# humanoid-16.net
KiCad netlist of a schematic drawn in EAGLE
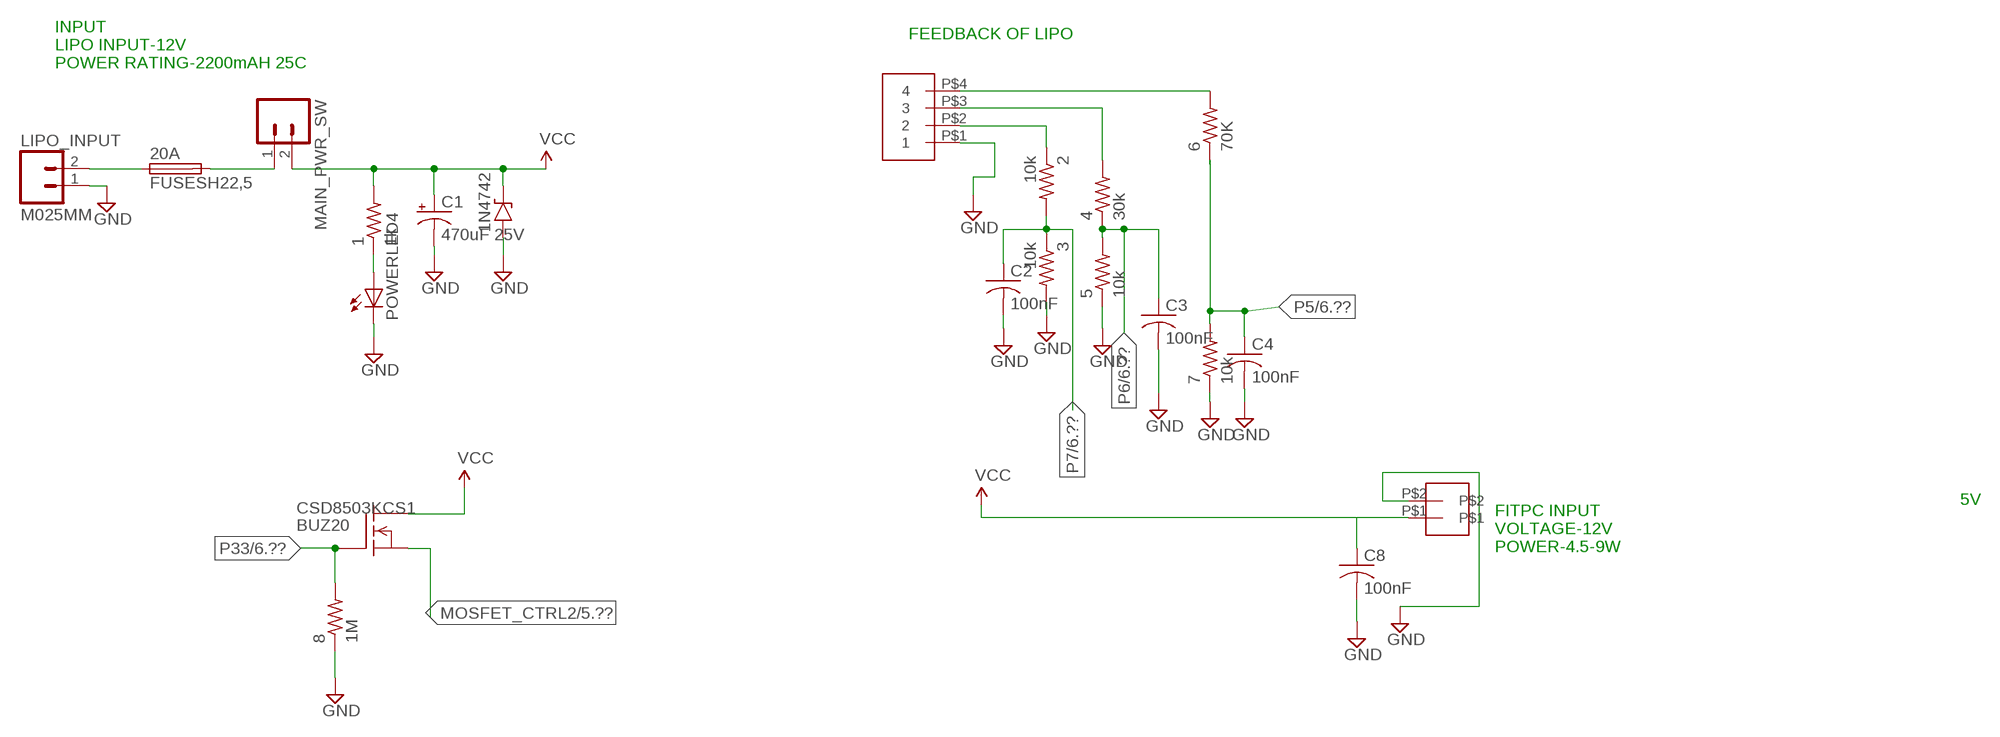
[diagram p0: schematic, sheet 1]
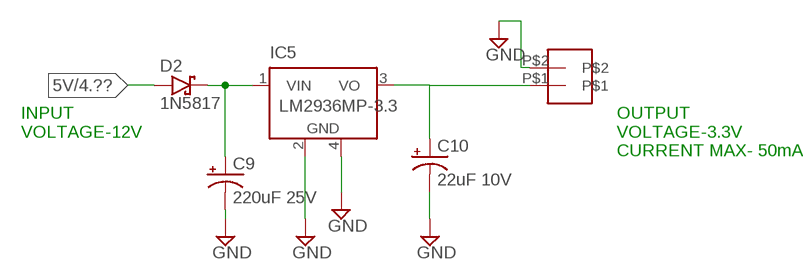
[diagram p1: schematic, sheet 2]
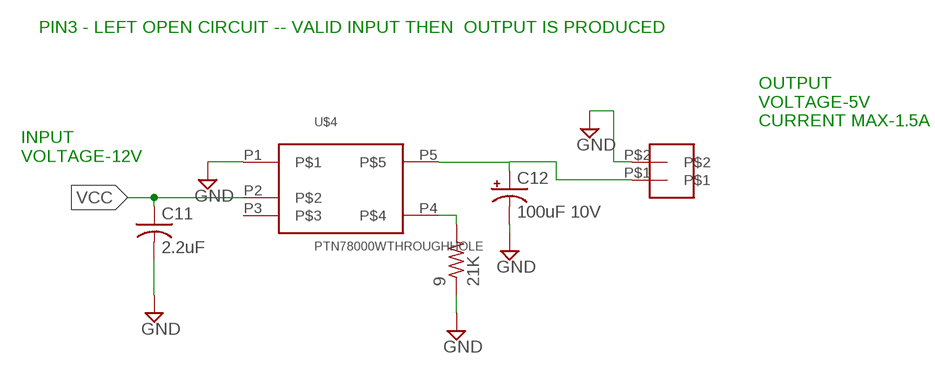
[diagram p2: schematic, sheet 3]
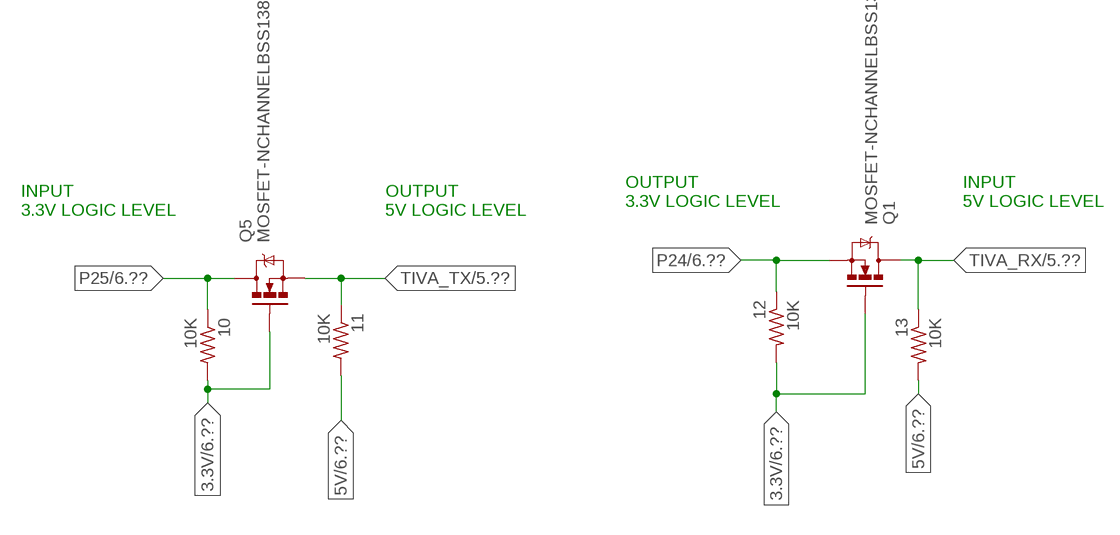
[diagram p3: schematic, sheet 4]
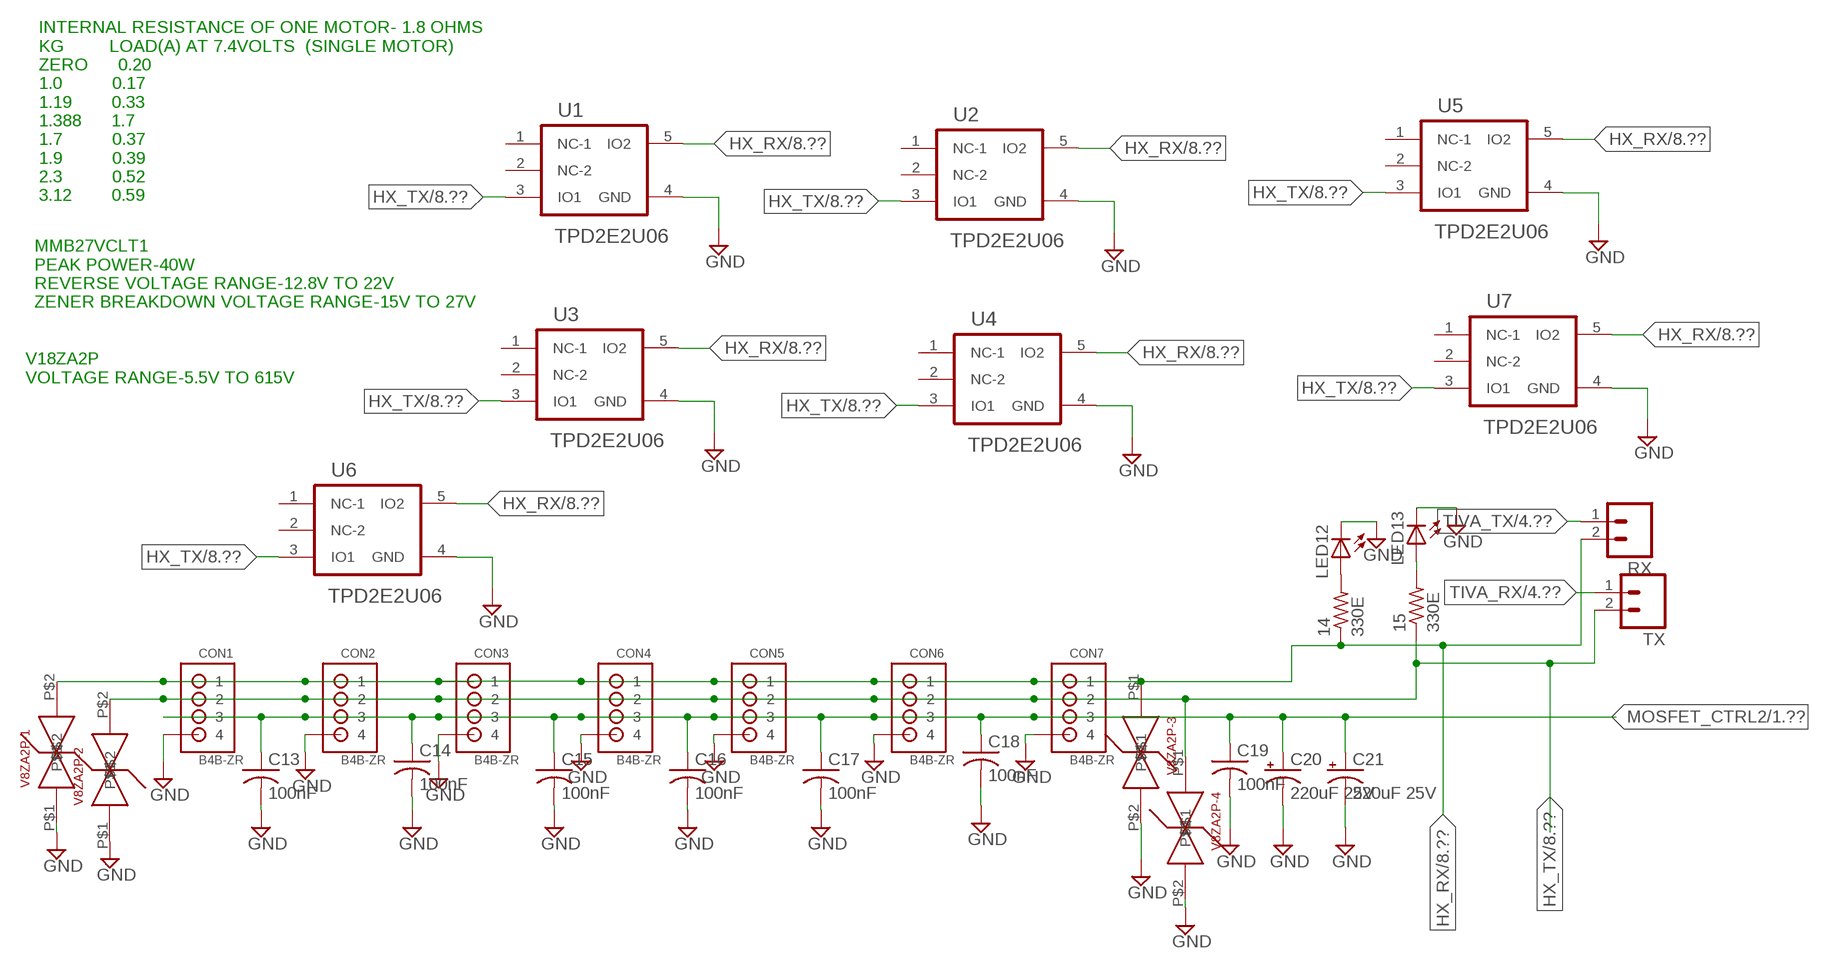
[diagram p4: schematic, sheet 5]
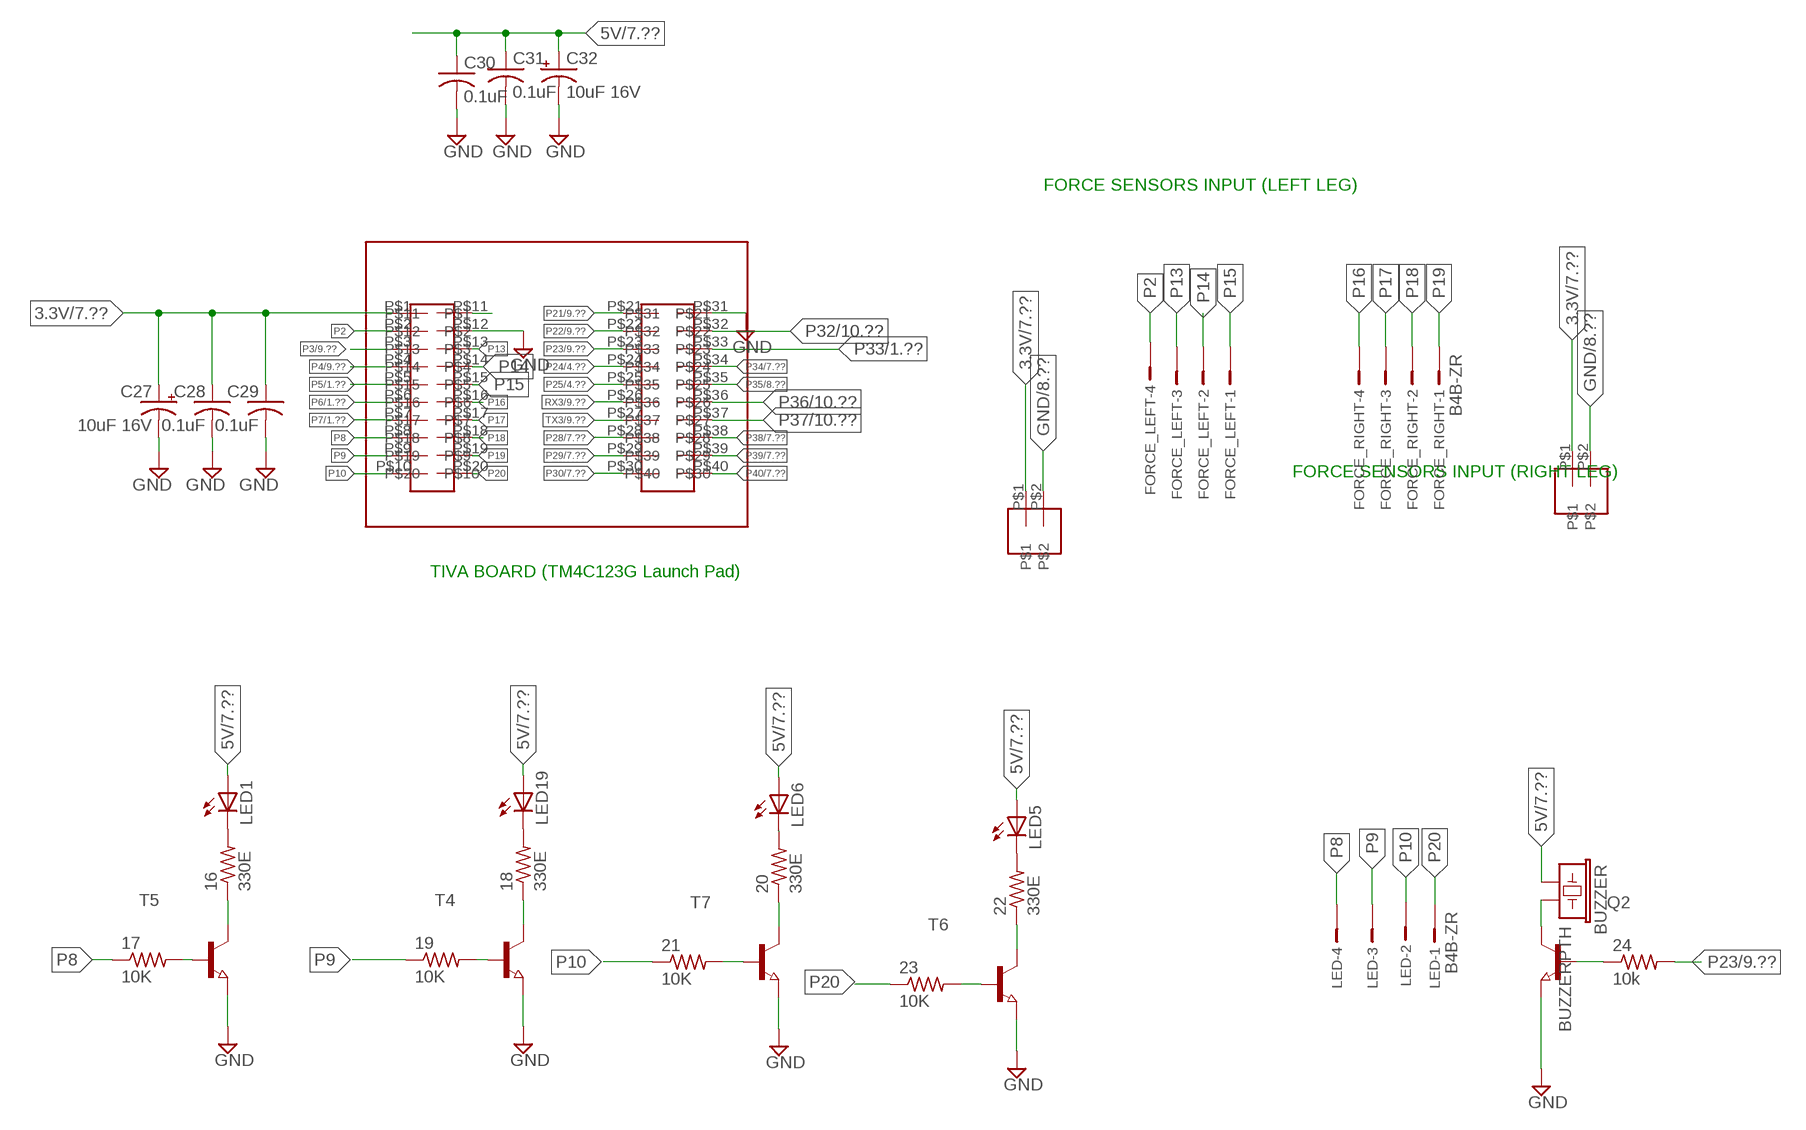
[diagram p5: schematic, sheet 6]
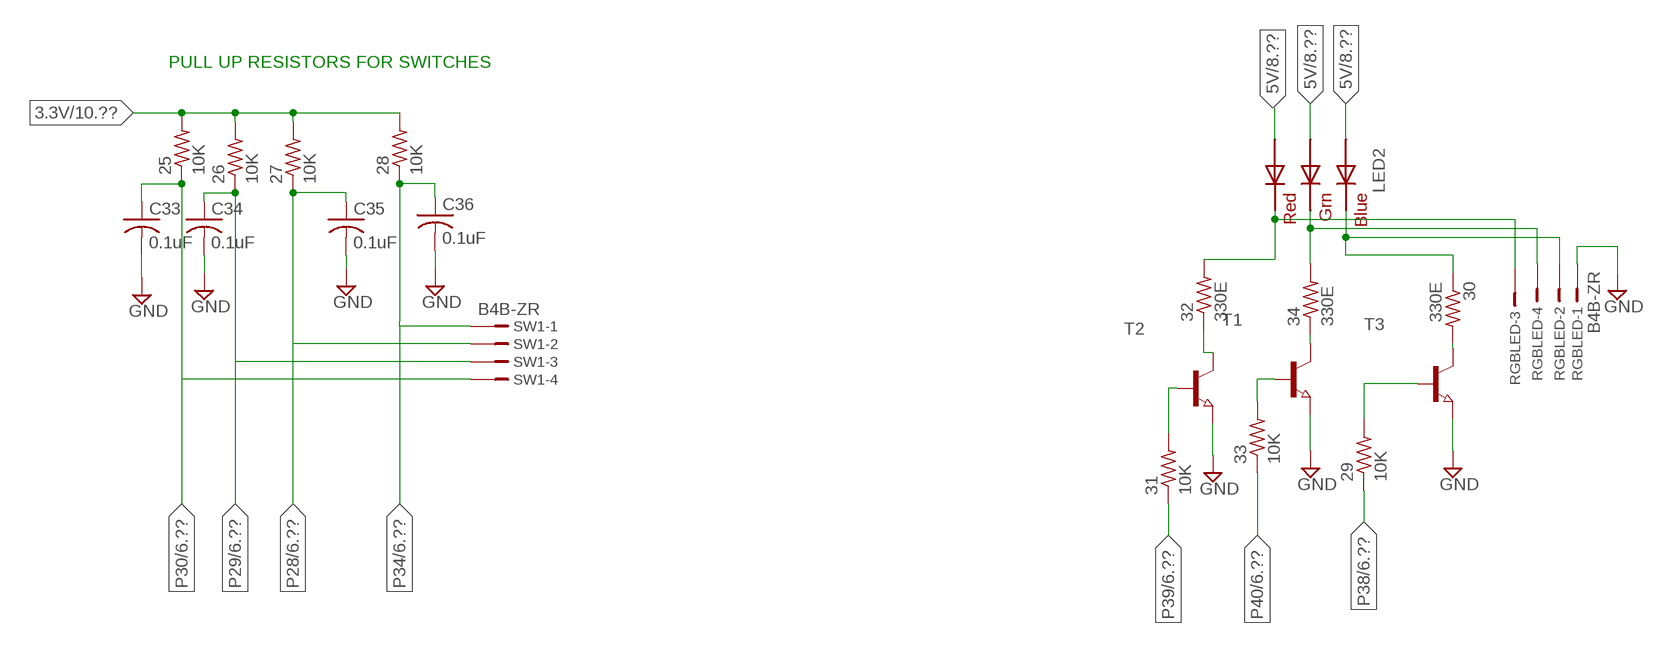
[diagram p6: schematic, sheet 7]
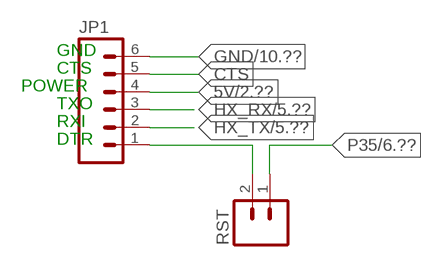
[diagram p7: schematic, sheet 8]
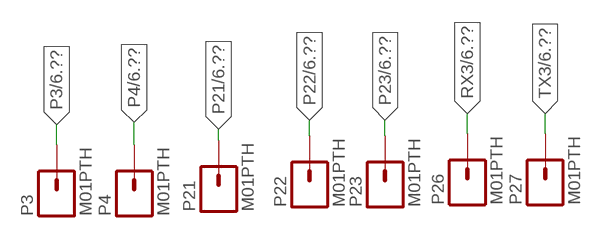
[diagram p8: schematic, sheet 9]
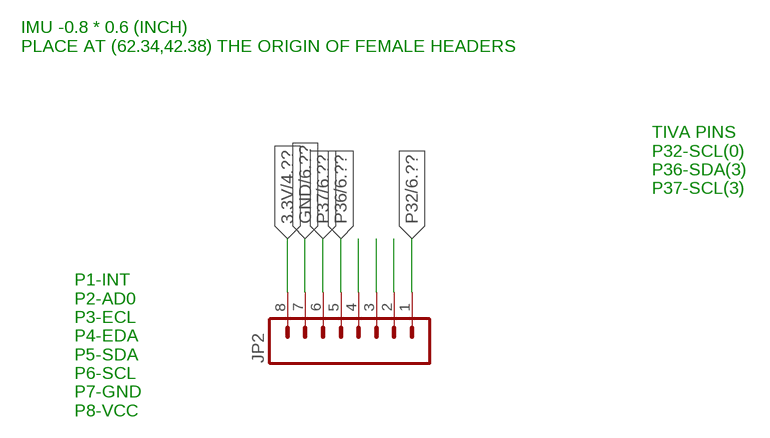
[diagram p9: schematic, sheet 10]

(export (version "E")
  (design (tool "Eeschema 10.0.6"))
  (components
    (comp (ref "3.3VL")
      (value "2PINRIGHT")
      (footprint "eagle-import:2PINRIGHT")
      (libsource (lib "eagle-import") (part "2PINRIGHT"))
    )
    (comp (ref "3.3VR")
      (value "2PINRIGHT")
      (footprint "eagle-import:2PINRIGHT")
      (libsource (lib "eagle-import") (part "2PINRIGHT"))
    )
    (comp (ref "16")
      (value "330E")
      (footprint "eagle-import:R0805")
      (libsource (lib "eagle-import") (part "R-US_R0805"))
    )
    (comp (ref "17")
      (value "10K")
      (footprint "eagle-import:R0805")
      (libsource (lib "eagle-import") (part "R-US_R0805"))
    )
    (comp (ref "18")
      (value "330E")
      (footprint "eagle-import:R0805")
      (libsource (lib "eagle-import") (part "R-US_R0805"))
    )
    (comp (ref "19")
      (value "10K")
      (footprint "eagle-import:R0805")
      (libsource (lib "eagle-import") (part "R-US_R0805"))
    )
    (comp (ref "20")
      (value "330E")
      (footprint "eagle-import:R0805")
      (libsource (lib "eagle-import") (part "R-US_R0805"))
    )
    (comp (ref "21")
      (value "10K")
      (footprint "eagle-import:R0805")
      (libsource (lib "eagle-import") (part "R-US_R0805"))
    )
    (comp (ref "22")
      (value "330E")
      (footprint "eagle-import:R0805")
      (libsource (lib "eagle-import") (part "R-US_R0805"))
    )
    (comp (ref "23")
      (value "10K")
      (footprint "eagle-import:R0805")
      (libsource (lib "eagle-import") (part "R-US_R0805"))
    )
    (comp (ref "24")
      (value "10k")
      (footprint "eagle-import:R0805")
      (libsource (lib "eagle-import") (part "R-US_R0805"))
    )
    (comp (ref "BUZZER")
      (value "BUZZERPTH")
      (footprint "eagle-import:BUZZER-12MM")
      (libsource (lib "eagle-import") (part "BUZZERPTH"))
    )
    (comp (ref "C27")
      (value "10uF 16V")
      (footprint "eagle-import:PANASONIC_B")
      (libsource (lib "eagle-import") (part "CPOL-USB"))
    )
    (comp (ref "C28")
      (value "0.1uF")
      (footprint "eagle-import:C1206")
      (libsource (lib "eagle-import") (part "resistor_C-USC1206"))
    )
    (comp (ref "C29")
      (value "0.1uF")
      (footprint "eagle-import:C1206")
      (libsource (lib "eagle-import") (part "resistor_C-USC1206"))
    )
    (comp (ref "C30")
      (value "0.1uF")
      (footprint "eagle-import:C1206")
      (libsource (lib "eagle-import") (part "resistor_C-USC1206"))
    )
    (comp (ref "C31")
      (value "0.1uF")
      (footprint "eagle-import:C1206")
      (libsource (lib "eagle-import") (part "resistor_C-USC1206"))
    )
    (comp (ref "C32")
      (value "10uF 16V")
      (footprint "eagle-import:PANASONIC_B")
      (libsource (lib "eagle-import") (part "CPOL-USB"))
    )
    (comp (ref "FORCE_LEFT")
      (value "B4B-ZR")
      (footprint "eagle-import:B4B-ZR")
      (fields
        (field (name "MF") "FARNELL")
        (field (name "MPN") "B4B-ZR(LF)(SN)")
        (field (name "OC_NEWARK") "unknown")
      )
      (libsource (lib "eagle-import") (part "?4B-ZRB"))
    )
    (comp (ref "FORCE_RIGHT")
      (value "B4B-ZR")
      (footprint "eagle-import:B4B-ZR")
      (fields
        (field (name "MF") "FARNELL")
        (field (name "MPN") "B4B-ZR(LF)(SN)")
        (field (name "OC_NEWARK") "unknown")
      )
      (libsource (lib "eagle-import") (part "?4B-ZRB"))
    )
    (comp (ref "LED")
      (value "B4B-ZR")
      (footprint "eagle-import:B4B-ZR")
      (fields
        (field (name "MF") "FARNELL")
        (field (name "MPN") "B4B-ZR(LF)(SN)")
        (field (name "OC_NEWARK") "unknown")
      )
      (libsource (lib "eagle-import") (part "?4B-ZRB"))
    )
    (comp (ref "LED1")
      (value "LEDCHIPLED_1206")
      (footprint "eagle-import:CHIPLED_1206")
      (libsource (lib "eagle-import") (part "LEDCHIPLED_1206"))
    )
    (comp (ref "LED5")
      (value "LEDCHIPLED_1206")
      (footprint "eagle-import:CHIPLED_1206")
      (libsource (lib "eagle-import") (part "LEDCHIPLED_1206"))
    )
    (comp (ref "LED6")
      (value "LEDCHIPLED_1206")
      (footprint "eagle-import:CHIPLED_1206")
      (libsource (lib "eagle-import") (part "LEDCHIPLED_1206"))
    )
    (comp (ref "LED19")
      (value "LEDCHIPLED_1206")
      (footprint "eagle-import:CHIPLED_1206")
      (libsource (lib "eagle-import") (part "LEDCHIPLED_1206"))
    )
    (comp (ref "Q2")
      (value "NPN-TRANSISTOR_SOT23")
      (footprint "eagle-import:SOT23")
      (libsource (lib "eagle-import") (part "NPN-TRANSISTOR_SOT23"))
    )
    (comp (ref "T4")
      (value "NPN-TRANSISTOR_SOT23")
      (footprint "eagle-import:SOT23")
      (libsource (lib "eagle-import") (part "NPN-TRANSISTOR_SOT23"))
    )
    (comp (ref "T5")
      (value "NPN-TRANSISTOR_SOT23")
      (footprint "eagle-import:SOT23")
      (libsource (lib "eagle-import") (part "NPN-TRANSISTOR_SOT23"))
    )
    (comp (ref "T6")
      (value "NPN-TRANSISTOR_SOT23")
      (footprint "eagle-import:SOT23")
      (libsource (lib "eagle-import") (part "NPN-TRANSISTOR_SOT23"))
    )
    (comp (ref "T7")
      (value "NPN-TRANSISTOR_SOT23")
      (footprint "eagle-import:SOT23")
      (libsource (lib "eagle-import") (part "NPN-TRANSISTOR_SOT23"))
    )
    (comp (ref "U$1")
      (value "TIVA")
      (footprint "eagle-import:TIVA")
      (libsource (lib "eagle-import") (part "TIVA"))
    )
    (comp (ref "10")
      (value "10K")
      (footprint "eagle-import:R0805")
      (libsource (lib "eagle-import") (part "R-US_R0805"))
    )
    (comp (ref "11")
      (value "10K")
      (footprint "eagle-import:R0805")
      (libsource (lib "eagle-import") (part "R-US_R0805"))
    )
    (comp (ref "12")
      (value "10K")
      (footprint "eagle-import:R0805")
      (libsource (lib "eagle-import") (part "R-US_R0805"))
    )
    (comp (ref "13")
      (value "10K")
      (footprint "eagle-import:R0805")
      (libsource (lib "eagle-import") (part "R-US_R0805"))
    )
    (comp (ref "Q1")
      (value "MOSFET-NCHANNELBSS138")
      (footprint "eagle-import:SOT23")
      (libsource (lib "eagle-import") (part "MOSFET-NCHANNELBSS138"))
    )
    (comp (ref "Q5")
      (value "MOSFET-NCHANNELBSS138")
      (footprint "eagle-import:SOT23")
      (libsource (lib "eagle-import") (part "MOSFET-NCHANNELBSS138"))
    )
    (comp (ref "14")
      (value "330E")
      (footprint "eagle-import:R0805")
      (libsource (lib "eagle-import") (part "R-US_R0805"))
    )
    (comp (ref "15")
      (value "330E")
      (footprint "eagle-import:R0805")
      (libsource (lib "eagle-import") (part "R-US_R0805"))
    )
    (comp (ref "C13")
      (value "100nF")
      (footprint "eagle-import:C1206")
      (fields (field (name "MANUFACTURER") "KEMET") (field (name "PARTNO") "C1206C104K5RACTU"))
      (libsource (lib "eagle-import") (part "C-USC1206"))
    )
    (comp (ref "C14")
      (value "100nF")
      (footprint "eagle-import:C1206")
      (fields (field (name "MANUFACTURER") "KEMET") (field (name "PARTNO") "C1206C104K5RACTU"))
      (libsource (lib "eagle-import") (part "C-USC1206"))
    )
    (comp (ref "C15")
      (value "100nF")
      (footprint "eagle-import:C1206")
      (fields (field (name "MANUFACTURER") "KEMET") (field (name "PARTNO") "C1206C104K5RACTU"))
      (libsource (lib "eagle-import") (part "C-USC1206"))
    )
    (comp (ref "C16")
      (value "100nF")
      (footprint "eagle-import:C1206")
      (fields (field (name "MANUFACTURER") "KEMET") (field (name "PARTNO") "C1206C104K5RACTU"))
      (libsource (lib "eagle-import") (part "C-USC1206"))
    )
    (comp (ref "C17")
      (value "100nF")
      (footprint "eagle-import:C1206")
      (fields (field (name "MANUFACTURER") "KEMET") (field (name "PARTNO") "C1206C104K5RACTU"))
      (libsource (lib "eagle-import") (part "C-USC1206"))
    )
    (comp (ref "C18")
      (value "100nF")
      (footprint "eagle-import:C1206")
      (fields (field (name "MANUFACTURER") "KEMET") (field (name "PARTNO") "C1206C104K5RACTU"))
      (libsource (lib "eagle-import") (part "C-USC1206"))
    )
    (comp (ref "C19")
      (value "100nF")
      (footprint "eagle-import:C1206")
      (fields (field (name "MANUFACTURER") "KEMET") (field (name "PARTNO") "C1206C104K5RACTU"))
      (libsource (lib "eagle-import") (part "C-USC1206"))
    )
    (comp (ref "C20")
      (value "220uF 25V")
      (footprint "eagle-import:PANASONIC_G")
      (fields
        (field (name "MANUFACTURER") " PANASONIC ELECTRONIC COMPONENTS")
        (field (name "MOUSER_PARTNO") "667-EEE-1EA221P")
        (field (name "PARTNO") "EEE-1EA221P")
      )
      (libsource (lib "eagle-import") (part "CPOL-USG"))
    )
    (comp (ref "C21")
      (value "220uF 25V")
      (footprint "eagle-import:PANASONIC_G")
      (fields
        (field (name "MANUFACTURER") " PANASONIC ELECTRONIC COMPONENTS")
        (field (name "MOUSER_PARTNO") "667-EEE-1EA221P")
        (field (name "PARTNO") "EEE-1EA221P")
      )
      (libsource (lib "eagle-import") (part "CPOL-USG"))
    )
    (comp (ref "CON1")
      (value "B4B-ZR")
      (footprint "eagle-import:B4B-ZR")
      (fields (field (name "MF") "FARNELL") (field (name "MPN") "B4B-ZR(LF)(SN)"))
      (libsource (lib "eagle-import") (part "B4B-ZR"))
    )
    (comp (ref "CON2")
      (value "B4B-ZR")
      (footprint "eagle-import:B4B-ZR")
      (fields (field (name "MF") "FARNELL") (field (name "MPN") "B4B-ZR(LF)(SN)"))
      (libsource (lib "eagle-import") (part "B4B-ZR"))
    )
    (comp (ref "CON3")
      (value "B4B-ZR")
      (footprint "eagle-import:B4B-ZR")
      (fields (field (name "MF") "FARNELL") (field (name "MPN") "B4B-ZR(LF)(SN)"))
      (libsource (lib "eagle-import") (part "B4B-ZR"))
    )
    (comp (ref "CON4")
      (value "B4B-ZR")
      (footprint "eagle-import:B4B-ZR")
      (fields (field (name "MF") "FARNELL") (field (name "MPN") "B4B-ZR(LF)(SN)"))
      (libsource (lib "eagle-import") (part "B4B-ZR"))
    )
    (comp (ref "CON5")
      (value "B4B-ZR")
      (footprint "eagle-import:B4B-ZR")
      (fields (field (name "MF") "FARNELL") (field (name "MPN") "B4B-ZR(LF)(SN)"))
      (libsource (lib "eagle-import") (part "B4B-ZR"))
    )
    (comp (ref "CON6")
      (value "B4B-ZR")
      (footprint "eagle-import:B4B-ZR")
      (fields (field (name "MF") "FARNELL") (field (name "MPN") "B4B-ZR(LF)(SN)"))
      (libsource (lib "eagle-import") (part "B4B-ZR"))
    )
    (comp (ref "CON7")
      (value "B4B-ZR")
      (footprint "eagle-import:B4B-ZR")
      (fields (field (name "MF") "FARNELL") (field (name "MPN") "B4B-ZR(LF)(SN)"))
      (libsource (lib "eagle-import") (part "B4B-ZR"))
    )
    (comp (ref "LED12")
      (value "LEDCHIPLED_1206")
      (footprint "eagle-import:CHIPLED_1206")
      (libsource (lib "eagle-import") (part "LEDCHIPLED_1206"))
    )
    (comp (ref "LED13")
      (value "LEDCHIPLED_1206")
      (footprint "eagle-import:CHIPLED_1206")
      (libsource (lib "eagle-import") (part "LEDCHIPLED_1206"))
    )
    (comp (ref "RX")
      (value "M02PTH")
      (footprint "eagle-import:1X02")
      (libsource (lib "eagle-import") (part "M02PTH"))
    )
    (comp (ref "TX")
      (value "M02PTH")
      (footprint "eagle-import:1X02")
      (libsource (lib "eagle-import") (part "M02PTH"))
    )
    (comp (ref "U1")
      (value "TPD2E2U06")
      (footprint "eagle-import:SOT50P160X60-5N")
      (fields (field (name "MPN") "TPD2E001IDRLRQ1"))
      (libsource (lib "eagle-import") (part "TPD2E2U06"))
    )
    (comp (ref "U2")
      (value "TPD2E2U06")
      (footprint "eagle-import:SOT50P160X60-5N")
      (fields (field (name "MPN") "TPD2E001IDRLRQ1"))
      (libsource (lib "eagle-import") (part "TPD2E2U06"))
    )
    (comp (ref "U3")
      (value "TPD2E2U06")
      (footprint "eagle-import:SOT50P160X60-5N")
      (fields (field (name "MPN") "TPD2E001IDRLRQ1"))
      (libsource (lib "eagle-import") (part "TPD2E2U06"))
    )
    (comp (ref "U4")
      (value "TPD2E2U06")
      (footprint "eagle-import:SOT50P160X60-5N")
      (fields (field (name "MPN") "TPD2E001IDRLRQ1"))
      (libsource (lib "eagle-import") (part "TPD2E2U06"))
    )
    (comp (ref "U5")
      (value "TPD2E2U06")
      (footprint "eagle-import:SOT50P160X60-5N")
      (fields (field (name "MPN") "TPD2E001IDRLRQ1"))
      (libsource (lib "eagle-import") (part "TPD2E2U06"))
    )
    (comp (ref "U6")
      (value "TPD2E2U06")
      (footprint "eagle-import:SOT50P160X60-5N")
      (fields (field (name "MPN") "TPD2E001IDRLRQ1"))
      (libsource (lib "eagle-import") (part "TPD2E2U06"))
    )
    (comp (ref "U7")
      (value "TPD2E2U06")
      (footprint "eagle-import:SOT50P160X60-5N")
      (fields (field (name "MPN") "TPD2E001IDRLRQ1"))
      (libsource (lib "eagle-import") (part "TPD2E2U06"))
    )
    (comp (ref "V8ZA2P-1")
      (value "V18ZA2P")
      (footprint "eagle-import:V18ZA2P")
      (libsource (lib "eagle-import") (part "V18ZA2P"))
    )
    (comp (ref "V8ZA2P-2")
      (value "V18ZA2P")
      (footprint "eagle-import:V18ZA2P")
      (libsource (lib "eagle-import") (part "V18ZA2P"))
    )
    (comp (ref "V8ZA2P-3")
      (value "V18ZA2P")
      (footprint "eagle-import:V18ZA2P")
      (libsource (lib "eagle-import") (part "V18ZA2P"))
    )
    (comp (ref "V8ZA2P-4")
      (value "V18ZA2P")
      (footprint "eagle-import:V18ZA2P")
      (libsource (lib "eagle-import") (part "V18ZA2P"))
    )
    (comp (ref "1")
      (value "1k")
      (footprint "eagle-import:R0805")
      (libsource (lib "eagle-import") (part "R-US_R0805"))
    )
    (comp (ref "1N4742")
      (value "1N47XX3")
      (footprint "eagle-import:DO41-3")
      (libsource (lib "eagle-import") (part "1N47XX3"))
    )
    (comp (ref "2")
      (value "10k")
      (footprint "eagle-import:R0805")
      (libsource (lib "eagle-import") (part "R-US_R0805"))
    )
    (comp (ref "3")
      (value "10k")
      (footprint "eagle-import:R0805")
      (libsource (lib "eagle-import") (part "R-US_R0805"))
    )
    (comp (ref "4")
      (value "30k")
      (footprint "eagle-import:R0805")
      (libsource (lib "eagle-import") (part "R-US_R0805"))
    )
    (comp (ref "5")
      (value "10k")
      (footprint "eagle-import:R0805")
      (libsource (lib "eagle-import") (part "R-US_R0805"))
    )
    (comp (ref "6")
      (value "70K")
      (footprint "eagle-import:R0805")
      (libsource (lib "eagle-import") (part "R-US_R0805"))
    )
    (comp (ref "7")
      (value "10k")
      (footprint "eagle-import:R0805")
      (libsource (lib "eagle-import") (part "R-US_R0805"))
    )
    (comp (ref "8")
      (value "1M")
      (footprint "eagle-import:R0805")
      (libsource (lib "eagle-import") (part "R-US_R0805"))
    )
    (comp (ref "20A")
      (value "FUSESH22,5")
      (footprint "eagle-import:SH22,5")
      (libsource (lib "eagle-import") (part "FUSESH22,5"))
    )
    (comp (ref "C1")
      (value "470uF 25V")
      (footprint "eagle-import:PANASONIC_G")
      (fields
        (field (name "MANUFACTURER") " PANASONIC ELECTRONIC COMPONENTS")
        (field (name "PARTNO") "EEEFK1E471AP")
      )
      (libsource (lib "eagle-import") (part "CPOL-USG"))
    )
    (comp (ref "C2")
      (value "100nF")
      (footprint "eagle-import:C1206")
      (fields (field (name "MANUFACTURER") "KEMET") (field (name "PARTNO") "C1206C104K5RACTU"))
      (libsource (lib "eagle-import") (part "C-USC1206"))
    )
    (comp (ref "C3")
      (value "100nF")
      (footprint "eagle-import:C1206")
      (fields (field (name "MANUFACTURER") "KEMET") (field (name "PARTNO") "C1206C104K5RACTU"))
      (libsource (lib "eagle-import") (part "C-USC1206"))
    )
    (comp (ref "C4")
      (value "100nF")
      (footprint "eagle-import:C1206")
      (fields (field (name "MANUFACTURER") "KEMET") (field (name "PARTNO") "C1206C104K5RACTU"))
      (libsource (lib "eagle-import") (part "C-USC1206"))
    )
    (comp (ref "C8")
      (value "100nF")
      (footprint "eagle-import:C1206")
      (fields (field (name "MANUFACTURER") "KEMET") (field (name "PARTNO") "C1206C104K5RACTU"))
      (libsource (lib "eagle-import") (part "C-USC1206"))
    )
    (comp (ref "CSD8503KCS1")
      (value "BUZ20")
      (footprint "eagle-import:TO220")
      (libsource (lib "eagle-import") (part "BUZ20"))
    )
    (comp (ref "FITPC")
      (value "2PINRIGHT")
      (footprint "eagle-import:2PINRIGHT")
      (libsource (lib "eagle-import") (part "2PINRIGHT"))
    )
    (comp (ref "LIPO_INPUT")
      (value "M025MM")
      (footprint "eagle-import:SCREWTERMINAL-5MM-2")
      (libsource (lib "eagle-import") (part "SparkFun-Connectors_M025MM"))
    )
    (comp (ref "MAIN_PWR_SW")
      (value "M02PTH")
      (footprint "eagle-import:1X02")
      (libsource (lib "eagle-import") (part "M02PTH"))
    )
    (comp (ref "POWERLED4")
      (value "LEDCHIPLED_1206")
      (footprint "eagle-import:CHIPLED_1206")
      (libsource (lib "eagle-import") (part "LEDCHIPLED_1206"))
    )
    (comp (ref "U$2")
      (value "4PINRIGHT")
      (footprint "eagle-import:4PINRIGHT")
      (libsource (lib "eagle-import") (part "4PINRIGHT"))
    )
    (comp (ref "JP1")
      (value "M06LOCK")
      (footprint "eagle-import:1X06_LOCK")
      (libsource (lib "eagle-import") (part "M06LOCK"))
    )
    (comp (ref "RST")
      (value "M02PTH")
      (footprint "eagle-import:1X02")
      (libsource (lib "eagle-import") (part "M02PTH"))
    )
    (comp (ref "5V1")
      (value "2PINRIGHT")
      (footprint "eagle-import:2PINRIGHT")
      (libsource (lib "eagle-import") (part "2PINRIGHT"))
    )
    (comp (ref "9")
      (value "21K")
      (footprint "eagle-import:R0805")
      (libsource (lib "eagle-import") (part "R-US_R0805"))
    )
    (comp (ref "C11")
      (value "2.2uF")
      (footprint "eagle-import:C1206")
      (fields
        (field (name "MANUFACTURER") "TDK")
        (field (name "MOUSER_PARTNO") "810-C1608X7R1A225K")
        (field (name "PARTNO") "C1608X7R1A225K080AC")
      )
      (libsource (lib "eagle-import") (part "resistor_C-USC1206"))
    )
    (comp (ref "C12")
      (value "100uF 10V")
      (footprint "eagle-import:PANASONIC_E")
      (fields
        (field (name "MANUFACTURER") "Panasonic")
        (field (name "MOUSER_PARTNO") " 667-EEE-HA1A101P")
        (field (name "PARTNO") "EEE-HA1A101P")
      )
      (libsource (lib "eagle-import") (part "CPOL-USE"))
    )
    (comp (ref "U$4")
      (value "PTN78000WTHROUGHHOLE")
      (footprint "eagle-import:PTN78000W")
      (libsource (lib "eagle-import") (part "PTN78000WTHROUGHHOLE"))
    )
    (comp (ref "25")
      (value "10K")
      (footprint "eagle-import:R0805")
      (libsource (lib "eagle-import") (part "R-US_R0805"))
    )
    (comp (ref "26")
      (value "10K")
      (footprint "eagle-import:R0805")
      (libsource (lib "eagle-import") (part "R-US_R0805"))
    )
    (comp (ref "27")
      (value "10K")
      (footprint "eagle-import:R0805")
      (libsource (lib "eagle-import") (part "R-US_R0805"))
    )
    (comp (ref "28")
      (value "10K")
      (footprint "eagle-import:R0805")
      (libsource (lib "eagle-import") (part "R-US_R0805"))
    )
    (comp (ref "29")
      (value "10K")
      (footprint "eagle-import:R0805")
      (libsource (lib "eagle-import") (part "R-US_R0805"))
    )
    (comp (ref "30")
      (value "330E")
      (footprint "eagle-import:R0805")
      (libsource (lib "eagle-import") (part "R-US_R0805"))
    )
    (comp (ref "31")
      (value "10K")
      (footprint "eagle-import:R0805")
      (libsource (lib "eagle-import") (part "R-US_R0805"))
    )
    (comp (ref "32")
      (value "330E")
      (footprint "eagle-import:R0805")
      (libsource (lib "eagle-import") (part "R-US_R0805"))
    )
    (comp (ref "33")
      (value "10K")
      (footprint "eagle-import:R0805")
      (libsource (lib "eagle-import") (part "R-US_R0805"))
    )
    (comp (ref "34")
      (value "330E")
      (footprint "eagle-import:R0805")
      (libsource (lib "eagle-import") (part "R-US_R0805"))
    )
    (comp (ref "C33")
      (value "0.1uF")
      (footprint "eagle-import:C1206")
      (fields
        (field (name "MANUFACTURER") "Kemet")
        (field (name "MOUSER_PARTNO") "80-C0805C104M5R")
        (field (name "PARTNO") "C0805C104M5RACTU")
      )
      (libsource (lib "eagle-import") (part "C-USC1206"))
    )
    (comp (ref "C34")
      (value "0.1uF")
      (footprint "eagle-import:C1206")
      (fields
        (field (name "MANUFACTURER") "Kemet")
        (field (name "MOUSER_PARTNO") "80-C0805C104M5R")
        (field (name "PARTNO") "C0805C104M5RACTU")
      )
      (libsource (lib "eagle-import") (part "C-USC1206"))
    )
    (comp (ref "C35")
      (value "0.1uF")
      (footprint "eagle-import:C1206")
      (fields
        (field (name "MANUFACTURER") "Kemet")
        (field (name "MOUSER_PARTNO") "80-C0805C104M5R")
        (field (name "PARTNO") "C0805C104M5RACTU")
      )
      (libsource (lib "eagle-import") (part "C-USC1206"))
    )
    (comp (ref "C36")
      (value "0.1uF")
      (footprint "eagle-import:C1206")
      (fields
        (field (name "MANUFACTURER") "Kemet")
        (field (name "MOUSER_PARTNO") "80-C0805C104M5R")
        (field (name "PARTNO") "C0805C104M5RACTU")
      )
      (libsource (lib "eagle-import") (part "C-USC1206"))
    )
    (comp (ref "LED2")
      (value "RGBLED5050")
      (footprint "eagle-import:RGBLED5050")
      (libsource (lib "eagle-import") (part "RGBLED5050"))
    )
    (comp (ref "RGBLED")
      (value "B4B-ZR")
      (footprint "eagle-import:B4B-ZR")
      (fields
        (field (name "MF") "FARNELL")
        (field (name "MPN") "B4B-ZR(LF)(SN)")
        (field (name "OC_NEWARK") "unknown")
      )
      (libsource (lib "eagle-import") (part "?4B-ZRB"))
    )
    (comp (ref "SW1")
      (value "B4B-ZR")
      (footprint "eagle-import:B4B-ZR")
      (fields
        (field (name "MF") "FARNELL")
        (field (name "MPN") "B4B-ZR(LF)(SN)")
        (field (name "OC_NEWARK") "unknown")
      )
      (libsource (lib "eagle-import") (part "?4B-ZRB"))
    )
    (comp (ref "T1")
      (value "NPN-TRANSISTOR_SOT23")
      (footprint "eagle-import:SOT23")
      (libsource (lib "eagle-import") (part "NPN-TRANSISTOR_SOT23"))
    )
    (comp (ref "T2")
      (value "NPN-TRANSISTOR_SOT23")
      (footprint "eagle-import:SOT23")
      (libsource (lib "eagle-import") (part "NPN-TRANSISTOR_SOT23"))
    )
    (comp (ref "T3")
      (value "NPN-TRANSISTOR_SOT23")
      (footprint "eagle-import:SOT23")
      (libsource (lib "eagle-import") (part "NPN-TRANSISTOR_SOT23"))
    )
    (comp (ref "JP2")
      (value "M081X08")
      (footprint "eagle-import:1X08")
      (libsource (lib "eagle-import") (part "M081X08"))
    )
    (comp (ref "P3")
      (value "M01PTH")
      (footprint "eagle-import:1X01")
      (libsource (lib "eagle-import") (part "M01PTH"))
    )
    (comp (ref "P4")
      (value "M01PTH")
      (footprint "eagle-import:1X01")
      (libsource (lib "eagle-import") (part "M01PTH"))
    )
    (comp (ref "P21")
      (value "M01PTH")
      (footprint "eagle-import:1X01")
      (libsource (lib "eagle-import") (part "M01PTH"))
    )
    (comp (ref "P22")
      (value "M01PTH")
      (footprint "eagle-import:1X01")
      (libsource (lib "eagle-import") (part "M01PTH"))
    )
    (comp (ref "P23")
      (value "M01PTH")
      (footprint "eagle-import:1X01")
      (libsource (lib "eagle-import") (part "M01PTH"))
    )
    (comp (ref "P26")
      (value "M01PTH")
      (footprint "eagle-import:1X01")
      (libsource (lib "eagle-import") (part "M01PTH"))
    )
    (comp (ref "P27")
      (value "M01PTH")
      (footprint "eagle-import:1X01")
      (libsource (lib "eagle-import") (part "M01PTH"))
    )
    (comp (ref "3.3V1")
      (value "2PINRIGHT")
      (footprint "eagle-import:2PINRIGHT")
      (libsource (lib "eagle-import") (part "2PINRIGHT"))
    )
    (comp (ref "C9")
      (value "220uF 25V")
      (footprint "eagle-import:PANASONIC_G")
      (fields
        (field (name "MANUFACTURER") " PANASONIC ELECTRONIC COMPONENTS")
        (field (name "MOUSER_PARTNO") "667-EEE-1EA221P")
        (field (name "PARTNO") "EEE-1EA221P")
      )
      (libsource (lib "eagle-import") (part "CPOL-USG"))
    )
    (comp (ref "C10")
      (value "22uF 10V")
      (footprint "eagle-import:PANASONIC_B")
      (fields
        (field (name "MANUFACTURER") " PANASONIC ELECTRONIC COMPONENTS")
        (field (name "PARTNO") "EEEFK1A220AR")
      )
      (libsource (lib "eagle-import") (part "CPOL-USB"))
    )
    (comp (ref "D2")
      (value "1N5817")
      (footprint "eagle-import:DO41-3")
      (libsource (lib "eagle-import") (part "1N5817"))
    )
    (comp (ref "IC5")
      (value "LM2936MP-3.3")
      (footprint "eagle-import:SOT223")
      (fields
        (field (name "MF") "NATIONAL SEMICONDUCTOR")
        (field (name "MPN") "LM2936MP-3.3/NOPB")
        (field (name "OC_NEWARK") "unknown")
      )
      (libsource (lib "eagle-import") (part "LM2936MP?-3.3"))
    )
  )
  (nets
    (net (code "1") (name "3.3V") (class "Default")
      (node (ref "10") (pin "2") (pinfunction "2_2") (pintype "passive"))
      (node (ref "12") (pin "2") (pinfunction "2_2") (pintype "passive"))
      (node (ref "25") (pin "2") (pinfunction "2_2") (pintype "passive"))
      (node (ref "26") (pin "2") (pinfunction "2_2") (pintype "passive"))
      (node (ref "27") (pin "2") (pinfunction "2_2") (pintype "passive"))
      (node (ref "28") (pin "2") (pinfunction "2_2") (pintype "passive"))
      (node (ref "3.3V1") (pin "P$1") (pinfunction "P$1_P$1") (pintype "bidirectional"))
      (node (ref "3.3VL") (pin "P$1") (pinfunction "P$1_P$1") (pintype "bidirectional"))
      (node (ref "3.3VR") (pin "P$1") (pinfunction "P$1_P$1") (pintype "bidirectional"))
      (node (ref "C10") (pin "+") (pinfunction "+_+") (pintype "passive"))
      (node (ref "C27") (pin "+") (pinfunction "+_+") (pintype "passive"))
      (node (ref "C28") (pin "1") (pinfunction "1_1") (pintype "passive"))
      (node (ref "C29") (pin "1") (pinfunction "1_1") (pintype "passive"))
      (node (ref "IC5") (pin "3") (pinfunction "VO_3") (pintype "passive"))
      (node (ref "JP2") (pin "8") (pinfunction "8_8") (pintype "passive"))
      (node (ref "Q1") (pin "1") (pinfunction "G_1") (pintype "passive"))
      (node (ref "Q5") (pin "1") (pinfunction "G_1") (pintype "passive"))
      (node (ref "U$1") (pin "P$1") (pinfunction "P$1_P$1") (pintype "bidirectional"))
    )
    (net (code "2") (name "5V") (class "Default")
      (node (ref "11") (pin "2") (pinfunction "2_2") (pintype "passive"))
      (node (ref "13") (pin "2") (pinfunction "2_2") (pintype "passive"))
      (node (ref "5V1") (pin "P$1") (pinfunction "P$1_P$1") (pintype "bidirectional"))
      (node (ref "BUZZER") (pin "+") (pinfunction "1_+") (pintype "passive"))
      (node (ref "C12") (pin "+") (pinfunction "+_+") (pintype "passive"))
      (node (ref "C30") (pin "1") (pinfunction "1_1") (pintype "passive"))
      (node (ref "C31") (pin "1") (pinfunction "1_1") (pintype "passive"))
      (node (ref "C32") (pin "+") (pinfunction "+_+") (pintype "passive"))
      (node (ref "D2") (pin "A") (pinfunction "A_A") (pintype "passive"))
      (node (ref "JP1") (pin "4") (pinfunction "4_4") (pintype "passive"))
      (node (ref "LED1") (pin "A") (pinfunction "A_A") (pintype "passive"))
      (node (ref "LED19") (pin "A") (pinfunction "A_A") (pintype "passive"))
      (node (ref "LED2") (pin "1") (pinfunction "GREEN_A_1") (pintype "bidirectional"))
      (node (ref "LED2") (pin "2") (pinfunction "RED_A_2") (pintype "bidirectional"))
      (node (ref "LED2") (pin "3") (pinfunction "BLUE_A_3") (pintype "bidirectional"))
      (node (ref "LED5") (pin "A") (pinfunction "A_A") (pintype "passive"))
      (node (ref "LED6") (pin "A") (pinfunction "A_A") (pintype "passive"))
      (node (ref "U$1") (pin "P$11") (pinfunction "P$11_P$11") (pintype "bidirectional"))
      (node (ref "U$4") (pin "P5") (pinfunction "P$5_P5") (pintype "bidirectional"))
    )
    (net (code "3") (name "CTS") (class "Default")
      (node (ref "JP1") (pin "5") (pinfunction "5_5") (pintype "passive"))
    )
    (net (code "4") (name "GND") (class "Default")
      (node (ref "1N4742") (pin "A") (pinfunction "A_A") (pintype "passive"))
      (node (ref "3") (pin "2") (pinfunction "2_2") (pintype "passive"))
      (node (ref "3.3V1") (pin "P$2") (pinfunction "P$2_P$2") (pintype "bidirectional"))
      (node (ref "3.3VL") (pin "P$2") (pinfunction "P$2_P$2") (pintype "bidirectional"))
      (node (ref "3.3VR") (pin "P$2") (pinfunction "P$2_P$2") (pintype "bidirectional"))
      (node (ref "5") (pin "1") (pinfunction "1_1") (pintype "passive"))
      (node (ref "5V1") (pin "P$2") (pinfunction "P$2_P$2") (pintype "bidirectional"))
      (node (ref "7") (pin "1") (pinfunction "1_1") (pintype "passive"))
      (node (ref "8") (pin "1") (pinfunction "1_1") (pintype "passive"))
      (node (ref "9") (pin "1") (pinfunction "1_1") (pintype "passive"))
      (node (ref "C1") (pin "-") (pinfunction "-_-") (pintype "passive"))
      (node (ref "C10") (pin "-") (pinfunction "-_-") (pintype "passive"))
      (node (ref "C11") (pin "2") (pinfunction "2_2") (pintype "passive"))
      (node (ref "C12") (pin "-") (pinfunction "-_-") (pintype "passive"))
      (node (ref "C13") (pin "2") (pinfunction "2_2") (pintype "passive"))
      (node (ref "C14") (pin "2") (pinfunction "2_2") (pintype "passive"))
      (node (ref "C15") (pin "2") (pinfunction "2_2") (pintype "passive"))
      (node (ref "C16") (pin "2") (pinfunction "2_2") (pintype "passive"))
      (node (ref "C17") (pin "2") (pinfunction "2_2") (pintype "passive"))
      (node (ref "C18") (pin "2") (pinfunction "2_2") (pintype "passive"))
      (node (ref "C19") (pin "2") (pinfunction "2_2") (pintype "passive"))
      (node (ref "C2") (pin "2") (pinfunction "2_2") (pintype "passive"))
      (node (ref "C20") (pin "-") (pinfunction "-_-") (pintype "passive"))
      (node (ref "C21") (pin "-") (pinfunction "-_-") (pintype "passive"))
      (node (ref "C27") (pin "-") (pinfunction "-_-") (pintype "passive"))
      (node (ref "C28") (pin "2") (pinfunction "2_2") (pintype "passive"))
      (node (ref "C29") (pin "2") (pinfunction "2_2") (pintype "passive"))
      (node (ref "C3") (pin "2") (pinfunction "2_2") (pintype "passive"))
      (node (ref "C30") (pin "2") (pinfunction "2_2") (pintype "passive"))
      (node (ref "C31") (pin "2") (pinfunction "2_2") (pintype "passive"))
      (node (ref "C32") (pin "-") (pinfunction "-_-") (pintype "passive"))
      (node (ref "C33") (pin "2") (pinfunction "2_2") (pintype "passive"))
      (node (ref "C34") (pin "2") (pinfunction "2_2") (pintype "passive"))
      (node (ref "C35") (pin "2") (pinfunction "2_2") (pintype "passive"))
      (node (ref "C36") (pin "2") (pinfunction "2_2") (pintype "passive"))
      (node (ref "C4") (pin "2") (pinfunction "2_2") (pintype "passive"))
      (node (ref "C8") (pin "2") (pinfunction "2_2") (pintype "passive"))
      (node (ref "C9") (pin "-") (pinfunction "-_-") (pintype "passive"))
      (node (ref "CON1") (pin "4") (pinfunction "4_4") (pintype "bidirectional"))
      (node (ref "CON2") (pin "4") (pinfunction "4_4") (pintype "bidirectional"))
      (node (ref "CON3") (pin "4") (pinfunction "4_4") (pintype "bidirectional"))
      (node (ref "CON4") (pin "4") (pinfunction "4_4") (pintype "bidirectional"))
      (node (ref "CON5") (pin "4") (pinfunction "4_4") (pintype "bidirectional"))
      (node (ref "CON6") (pin "4") (pinfunction "4_4") (pintype "bidirectional"))
      (node (ref "CON7") (pin "4") (pinfunction "4_4") (pintype "bidirectional"))
      (node (ref "FITPC") (pin "P$2") (pinfunction "P$2_P$2") (pintype "bidirectional"))
      (node (ref "IC5") (pin "2") (pinfunction "GND_2") (pintype "passive"))
      (node (ref "IC5") (pin "4") (pinfunction "GND_4") (pintype "passive"))
      (node (ref "JP1") (pin "6") (pinfunction "6_6") (pintype "passive"))
      (node (ref "JP2") (pin "7") (pinfunction "7_7") (pintype "passive"))
      (node (ref "LED12") (pin "C") (pinfunction "C_C") (pintype "passive"))
      (node (ref "LED13") (pin "C") (pinfunction "C_C") (pintype "passive"))
      (node (ref "LIPO_INPUT") (pin "1") (pinfunction "1_1") (pintype "passive"))
      (node (ref "POWERLED4") (pin "C") (pinfunction "C_C") (pintype "passive"))
      (node (ref "Q2") (pin "2") (pinfunction "E_2") (pintype "passive"))
      (node (ref "RGBLED") (pin "1") (pinfunction "1_1") (pintype "passive"))
      (node (ref "T1") (pin "2") (pinfunction "E_2") (pintype "passive"))
      (node (ref "T2") (pin "2") (pinfunction "E_2") (pintype "passive"))
      (node (ref "T3") (pin "2") (pinfunction "E_2") (pintype "passive"))
      (node (ref "T4") (pin "2") (pinfunction "E_2") (pintype "passive"))
      (node (ref "T5") (pin "2") (pinfunction "E_2") (pintype "passive"))
      (node (ref "T6") (pin "2") (pinfunction "E_2") (pintype "passive"))
      (node (ref "T7") (pin "2") (pinfunction "E_2") (pintype "passive"))
      (node (ref "U$1") (pin "P$12") (pinfunction "P$12_P$12") (pintype "bidirectional"))
      (node (ref "U$1") (pin "P$31") (pinfunction "P$31_P$31") (pintype "bidirectional"))
      (node (ref "U$2") (pin "P$1") (pinfunction "1_P$1") (pintype "bidirectional"))
      (node (ref "U$4") (pin "P1") (pinfunction "P$1_P1") (pintype "bidirectional"))
      (node (ref "U1") (pin "4") (pinfunction "GND_4") (pintype "bidirectional"))
      (node (ref "U2") (pin "4") (pinfunction "GND_4") (pintype "bidirectional"))
      (node (ref "U3") (pin "4") (pinfunction "GND_4") (pintype "bidirectional"))
      (node (ref "U4") (pin "4") (pinfunction "GND_4") (pintype "bidirectional"))
      (node (ref "U5") (pin "4") (pinfunction "GND_4") (pintype "bidirectional"))
      (node (ref "U6") (pin "4") (pinfunction "GND_4") (pintype "bidirectional"))
      (node (ref "U7") (pin "4") (pinfunction "GND_4") (pintype "bidirectional"))
      (node (ref "V8ZA2P-1") (pin "P$1") (pinfunction "P$1_P$1") (pintype "bidirectional"))
      (node (ref "V8ZA2P-2") (pin "P$1") (pinfunction "P$1_P$1") (pintype "bidirectional"))
      (node (ref "V8ZA2P-3") (pin "P$2") (pinfunction "P$2_P$2") (pintype "bidirectional"))
      (node (ref "V8ZA2P-4") (pin "P$2") (pinfunction "P$2_P$2") (pintype "bidirectional"))
    )
    (net (code "5") (name "HX_RX") (class "Default")
      (node (ref "14") (pin "1") (pinfunction "1_1") (pintype "passive"))
      (node (ref "CON1") (pin "1") (pinfunction "1_1") (pintype "bidirectional"))
      (node (ref "CON2") (pin "1") (pinfunction "1_1") (pintype "bidirectional"))
      (node (ref "CON3") (pin "1") (pinfunction "1_1") (pintype "bidirectional"))
      (node (ref "CON4") (pin "1") (pinfunction "1_1") (pintype "bidirectional"))
      (node (ref "CON5") (pin "1") (pinfunction "1_1") (pintype "bidirectional"))
      (node (ref "CON6") (pin "1") (pinfunction "1_1") (pintype "bidirectional"))
      (node (ref "CON7") (pin "1") (pinfunction "1_1") (pintype "bidirectional"))
      (node (ref "JP1") (pin "3") (pinfunction "3_3") (pintype "passive"))
      (node (ref "RX") (pin "2") (pinfunction "2_2") (pintype "passive"))
      (node (ref "U1") (pin "5") (pinfunction "IO2_5") (pintype "bidirectional"))
      (node (ref "U2") (pin "5") (pinfunction "IO2_5") (pintype "bidirectional"))
      (node (ref "U3") (pin "5") (pinfunction "IO2_5") (pintype "bidirectional"))
      (node (ref "U4") (pin "5") (pinfunction "IO2_5") (pintype "bidirectional"))
      (node (ref "U5") (pin "5") (pinfunction "IO2_5") (pintype "bidirectional"))
      (node (ref "U6") (pin "5") (pinfunction "IO2_5") (pintype "bidirectional"))
      (node (ref "U7") (pin "5") (pinfunction "IO2_5") (pintype "bidirectional"))
      (node (ref "V8ZA2P-1") (pin "P$2") (pinfunction "P$2_P$2") (pintype "bidirectional"))
      (node (ref "V8ZA2P-3") (pin "P$1") (pinfunction "P$1_P$1") (pintype "bidirectional"))
    )
    (net (code "6") (name "HX_TX") (class "Default")
      (node (ref "15") (pin "1") (pinfunction "1_1") (pintype "passive"))
      (node (ref "CON1") (pin "2") (pinfunction "2_2") (pintype "bidirectional"))
      (node (ref "CON2") (pin "2") (pinfunction "2_2") (pintype "bidirectional"))
      (node (ref "CON3") (pin "2") (pinfunction "2_2") (pintype "bidirectional"))
      (node (ref "CON4") (pin "2") (pinfunction "2_2") (pintype "bidirectional"))
      (node (ref "CON5") (pin "2") (pinfunction "2_2") (pintype "bidirectional"))
      (node (ref "CON6") (pin "2") (pinfunction "2_2") (pintype "bidirectional"))
      (node (ref "CON7") (pin "2") (pinfunction "2_2") (pintype "bidirectional"))
      (node (ref "JP1") (pin "2") (pinfunction "2_2") (pintype "passive"))
      (node (ref "TX") (pin "2") (pinfunction "2_2") (pintype "passive"))
      (node (ref "U1") (pin "3") (pinfunction "IO1_3") (pintype "input"))
      (node (ref "U2") (pin "3") (pinfunction "IO1_3") (pintype "input"))
      (node (ref "U3") (pin "3") (pinfunction "IO1_3") (pintype "input"))
      (node (ref "U4") (pin "3") (pinfunction "IO1_3") (pintype "input"))
      (node (ref "U5") (pin "3") (pinfunction "IO1_3") (pintype "input"))
      (node (ref "U6") (pin "3") (pinfunction "IO1_3") (pintype "input"))
      (node (ref "U7") (pin "3") (pinfunction "IO1_3") (pintype "input"))
      (node (ref "V8ZA2P-2") (pin "P$2") (pinfunction "P$2_P$2") (pintype "bidirectional"))
      (node (ref "V8ZA2P-4") (pin "P$1") (pinfunction "P$1_P$1") (pintype "bidirectional"))
    )
    (net (code "7") (name "MOSFET_CTRL2") (class "Default")
      (node (ref "C13") (pin "1") (pinfunction "1_1") (pintype "passive"))
      (node (ref "C14") (pin "1") (pinfunction "1_1") (pintype "passive"))
      (node (ref "C15") (pin "1") (pinfunction "1_1") (pintype "passive"))
      (node (ref "C16") (pin "1") (pinfunction "1_1") (pintype "passive"))
      (node (ref "C17") (pin "1") (pinfunction "1_1") (pintype "passive"))
      (node (ref "C18") (pin "1") (pinfunction "1_1") (pintype "passive"))
      (node (ref "C19") (pin "1") (pinfunction "1_1") (pintype "passive"))
      (node (ref "C20") (pin "+") (pinfunction "+_+") (pintype "passive"))
      (node (ref "C21") (pin "+") (pinfunction "+_+") (pintype "passive"))
      (node (ref "CON1") (pin "3") (pinfunction "3_3") (pintype "bidirectional"))
      (node (ref "CON2") (pin "3") (pinfunction "3_3") (pintype "bidirectional"))
      (node (ref "CON3") (pin "3") (pinfunction "3_3") (pintype "bidirectional"))
      (node (ref "CON4") (pin "3") (pinfunction "3_3") (pintype "bidirectional"))
      (node (ref "CON5") (pin "3") (pinfunction "3_3") (pintype "bidirectional"))
      (node (ref "CON6") (pin "3") (pinfunction "3_3") (pintype "bidirectional"))
      (node (ref "CON7") (pin "3") (pinfunction "3_3") (pintype "bidirectional"))
      (node (ref "CSD8503KCS1") (pin "3") (pinfunction "S_3") (pintype "passive"))
    )
    (net (code "8") (name "Net-(1-Pad1)") (class "Default")
      (node (ref "1") (pin "1") (pinfunction "1_1") (pintype "passive"))
      (node (ref "POWERLED4") (pin "A") (pinfunction "A_A") (pintype "passive"))
    )
    (net (code "9") (name "Net-(14-Pad2)") (class "Default")
      (node (ref "14") (pin "2") (pinfunction "2_2") (pintype "passive"))
      (node (ref "LED12") (pin "A") (pinfunction "A_A") (pintype "passive"))
    )
    (net (code "10") (name "Net-(15-Pad2)") (class "Default")
      (node (ref "15") (pin "2") (pinfunction "2_2") (pintype "passive"))
      (node (ref "LED13") (pin "A") (pinfunction "A_A") (pintype "passive"))
    )
    (net (code "11") (name "Net-(16-Pad2)") (class "Default")
      (node (ref "16") (pin "2") (pinfunction "2_2") (pintype "passive"))
      (node (ref "LED1") (pin "C") (pinfunction "C_C") (pintype "passive"))
    )
    (net (code "12") (name "Net-(18-Pad2)") (class "Default")
      (node (ref "18") (pin "2") (pinfunction "2_2") (pintype "passive"))
      (node (ref "LED19") (pin "C") (pinfunction "C_C") (pintype "passive"))
    )
    (net (code "13") (name "Net-(20-Pad2)") (class "Default")
      (node (ref "20") (pin "2") (pinfunction "2_2") (pintype "passive"))
      (node (ref "LED6") (pin "C") (pinfunction "C_C") (pintype "passive"))
    )
    (net (code "14") (name "Net-(20A-Pad1)") (class "Default")
      (node (ref "20A") (pin "1") (pinfunction "1_1") (pintype "passive"))
      (node (ref "LIPO_INPUT") (pin "2") (pinfunction "2_2") (pintype "passive"))
    )
    (net (code "15") (name "Net-(20A-Pad2)") (class "Default")
      (node (ref "20A") (pin "2") (pinfunction "2_2") (pintype "passive"))
      (node (ref "MAIN_PWR_SW") (pin "1") (pinfunction "1_1") (pintype "passive"))
    )
    (net (code "16") (name "Net-(22-Pad2)") (class "Default")
      (node (ref "22") (pin "2") (pinfunction "2_2") (pintype "passive"))
      (node (ref "LED5") (pin "C") (pinfunction "C_C") (pintype "passive"))
    )
    (net (code "17") (name "Net-(BUZZER-2)") (class "Default")
      (node (ref "BUZZER") (pin "-") (pinfunction "2_-") (pintype "passive"))
      (node (ref "Q2") (pin "3") (pinfunction "C_3") (pintype "passive"))
    )
    (net (code "18") (name "Net-(IC5-VIN)") (class "Default")
      (node (ref "C9") (pin "+") (pinfunction "+_+") (pintype "passive"))
      (node (ref "D2") (pin "C") (pinfunction "C_C") (pintype "passive"))
      (node (ref "IC5") (pin "1") (pinfunction "VIN_1") (pintype "input"))
    )
    (net (code "19") (name "Net-(JP1-Pad1)") (class "Default")
      (node (ref "JP1") (pin "1") (pinfunction "1_1") (pintype "passive"))
      (node (ref "RST") (pin "2") (pinfunction "2_2") (pintype "passive"))
    )
    (net (code "20") (name "Net-(LED2-BLUE_C)") (class "Default")
      (node (ref "30") (pin "1") (pinfunction "1_1") (pintype "passive"))
      (node (ref "LED2") (pin "4") (pinfunction "BLUE_C_4") (pintype "bidirectional"))
      (node (ref "RGBLED") (pin "2") (pinfunction "1_2") (pintype "passive"))
    )
    (net (code "21") (name "Net-(LED2-GREEN_C)") (class "Default")
      (node (ref "34") (pin "2") (pinfunction "2_2") (pintype "passive"))
      (node (ref "LED2") (pin "6") (pinfunction "GREEN_C_6") (pintype "bidirectional"))
      (node (ref "RGBLED") (pin "4") (pinfunction "1_4") (pintype "passive"))
    )
    (net (code "22") (name "Net-(LED2-RED_C)") (class "Default")
      (node (ref "32") (pin "2") (pinfunction "2_2") (pintype "passive"))
      (node (ref "LED2") (pin "5") (pinfunction "RED_C_5") (pintype "bidirectional"))
      (node (ref "RGBLED") (pin "3") (pinfunction "1_3") (pintype "passive"))
    )
    (net (code "23") (name "Net-(Q2-B)") (class "Default")
      (node (ref "24") (pin "1") (pinfunction "1_1") (pintype "passive"))
      (node (ref "Q2") (pin "1") (pinfunction "B_1") (pintype "passive"))
    )
    (net (code "24") (name "Net-(T1-B)") (class "Default")
      (node (ref "33") (pin "2") (pinfunction "2_2") (pintype "passive"))
      (node (ref "T1") (pin "1") (pinfunction "B_1") (pintype "passive"))
    )
    (net (code "25") (name "Net-(T1-C)") (class "Default")
      (node (ref "34") (pin "1") (pinfunction "1_1") (pintype "passive"))
      (node (ref "T1") (pin "3") (pinfunction "C_3") (pintype "passive"))
    )
    (net (code "26") (name "Net-(T2-B)") (class "Default")
      (node (ref "31") (pin "2") (pinfunction "2_2") (pintype "passive"))
      (node (ref "T2") (pin "1") (pinfunction "B_1") (pintype "passive"))
    )
    (net (code "27") (name "Net-(T2-C)") (class "Default")
      (node (ref "32") (pin "1") (pinfunction "1_1") (pintype "passive"))
      (node (ref "T2") (pin "3") (pinfunction "C_3") (pintype "passive"))
    )
    (net (code "28") (name "Net-(T3-B)") (class "Default")
      (node (ref "29") (pin "2") (pinfunction "2_2") (pintype "passive"))
      (node (ref "T3") (pin "1") (pinfunction "B_1") (pintype "passive"))
    )
    (net (code "29") (name "Net-(T3-C)") (class "Default")
      (node (ref "30") (pin "2") (pinfunction "2_2") (pintype "passive"))
      (node (ref "T3") (pin "3") (pinfunction "C_3") (pintype "passive"))
    )
    (net (code "30") (name "Net-(T4-B)") (class "Default")
      (node (ref "19") (pin "2") (pinfunction "2_2") (pintype "passive"))
      (node (ref "T4") (pin "1") (pinfunction "B_1") (pintype "passive"))
    )
    (net (code "31") (name "Net-(T4-C)") (class "Default")
      (node (ref "18") (pin "1") (pinfunction "1_1") (pintype "passive"))
      (node (ref "T4") (pin "3") (pinfunction "C_3") (pintype "passive"))
    )
    (net (code "32") (name "Net-(T5-B)") (class "Default")
      (node (ref "17") (pin "2") (pinfunction "2_2") (pintype "passive"))
      (node (ref "T5") (pin "1") (pinfunction "B_1") (pintype "passive"))
    )
    (net (code "33") (name "Net-(T5-C)") (class "Default")
      (node (ref "16") (pin "1") (pinfunction "1_1") (pintype "passive"))
      (node (ref "T5") (pin "3") (pinfunction "C_3") (pintype "passive"))
    )
    (net (code "34") (name "Net-(T6-B)") (class "Default")
      (node (ref "23") (pin "2") (pinfunction "2_2") (pintype "passive"))
      (node (ref "T6") (pin "1") (pinfunction "B_1") (pintype "passive"))
    )
    (net (code "35") (name "Net-(T6-C)") (class "Default")
      (node (ref "22") (pin "1") (pinfunction "1_1") (pintype "passive"))
      (node (ref "T6") (pin "3") (pinfunction "C_3") (pintype "passive"))
    )
    (net (code "36") (name "Net-(T7-B)") (class "Default")
      (node (ref "21") (pin "2") (pinfunction "2_2") (pintype "passive"))
      (node (ref "T7") (pin "1") (pinfunction "B_1") (pintype "passive"))
    )
    (net (code "37") (name "Net-(T7-C)") (class "Default")
      (node (ref "20") (pin "1") (pinfunction "1_1") (pintype "passive"))
      (node (ref "T7") (pin "3") (pinfunction "C_3") (pintype "passive"))
    )
    (net (code "38") (name "Net-(U$2-2)") (class "Default")
      (node (ref "2") (pin "1") (pinfunction "1_1") (pintype "passive"))
      (node (ref "U$2") (pin "P$2") (pinfunction "2_P$2") (pintype "bidirectional"))
    )
    (net (code "39") (name "Net-(U$2-3)") (class "Default")
      (node (ref "4") (pin "2") (pinfunction "2_2") (pintype "passive"))
      (node (ref "U$2") (pin "P$3") (pinfunction "3_P$3") (pintype "bidirectional"))
    )
    (net (code "40") (name "Net-(U$2-4)") (class "Default")
      (node (ref "6") (pin "2") (pinfunction "2_2") (pintype "passive"))
      (node (ref "U$2") (pin "P$4") (pinfunction "4_P$4") (pintype "bidirectional"))
    )
    (net (code "41") (name "Net-(U$4-P$4)") (class "Default")
      (node (ref "9") (pin "2") (pinfunction "2_2") (pintype "passive"))
      (node (ref "U$4") (pin "P4") (pinfunction "P$4_P4") (pintype "bidirectional"))
    )
    (net (code "42") (name "P2") (class "Default")
      (node (ref "FORCE_LEFT") (pin "4") (pinfunction "1_4") (pintype "passive"))
      (node (ref "U$1") (pin "P$2") (pinfunction "P$2_P$2") (pintype "bidirectional"))
    )
    (net (code "43") (name "P3") (class "Default")
      (node (ref "P3") (pin "1") (pinfunction "1_1") (pintype "passive"))
      (node (ref "U$1") (pin "P$3") (pinfunction "P$3_P$3") (pintype "bidirectional"))
    )
    (net (code "44") (name "P4") (class "Default")
      (node (ref "P4") (pin "1") (pinfunction "1_1") (pintype "passive"))
      (node (ref "U$1") (pin "P$4") (pinfunction "P$4_P$4") (pintype "bidirectional"))
    )
    (net (code "45") (name "P5") (class "Default")
      (node (ref "6") (pin "1") (pinfunction "1_1") (pintype "passive"))
      (node (ref "7") (pin "2") (pinfunction "2_2") (pintype "passive"))
      (node (ref "C4") (pin "1") (pinfunction "1_1") (pintype "passive"))
      (node (ref "U$1") (pin "P$5") (pinfunction "P$5_P$5") (pintype "bidirectional"))
    )
    (net (code "46") (name "P6") (class "Default")
      (node (ref "4") (pin "1") (pinfunction "1_1") (pintype "passive"))
      (node (ref "5") (pin "2") (pinfunction "2_2") (pintype "passive"))
      (node (ref "C3") (pin "1") (pinfunction "1_1") (pintype "passive"))
      (node (ref "U$1") (pin "P$6") (pinfunction "P$6_P$6") (pintype "bidirectional"))
    )
    (net (code "47") (name "P7") (class "Default")
      (node (ref "2") (pin "2") (pinfunction "2_2") (pintype "passive"))
      (node (ref "3") (pin "1") (pinfunction "1_1") (pintype "passive"))
      (node (ref "C2") (pin "1") (pinfunction "1_1") (pintype "passive"))
      (node (ref "U$1") (pin "P$7") (pinfunction "P$7_P$7") (pintype "bidirectional"))
    )
    (net (code "48") (name "P8") (class "Default")
      (node (ref "17") (pin "1") (pinfunction "1_1") (pintype "passive"))
      (node (ref "LED") (pin "4") (pinfunction "1_4") (pintype "passive"))
      (node (ref "U$1") (pin "P$8") (pinfunction "P$8_P$8") (pintype "bidirectional"))
    )
    (net (code "49") (name "P9") (class "Default")
      (node (ref "19") (pin "1") (pinfunction "1_1") (pintype "passive"))
      (node (ref "LED") (pin "3") (pinfunction "1_3") (pintype "passive"))
      (node (ref "U$1") (pin "P$9") (pinfunction "P$9_P$9") (pintype "bidirectional"))
    )
    (net (code "50") (name "P10") (class "Default")
      (node (ref "21") (pin "1") (pinfunction "1_1") (pintype "passive"))
      (node (ref "LED") (pin "2") (pinfunction "1_2") (pintype "passive"))
      (node (ref "U$1") (pin "P$10") (pinfunction "P$10_P$10") (pintype "bidirectional"))
    )
    (net (code "51") (name "P13") (class "Default")
      (node (ref "FORCE_LEFT") (pin "3") (pinfunction "1_3") (pintype "passive"))
      (node (ref "U$1") (pin "P$13") (pinfunction "P$13_P$13") (pintype "bidirectional"))
    )
    (net (code "52") (name "P14") (class "Default")
      (node (ref "FORCE_LEFT") (pin "2") (pinfunction "1_2") (pintype "passive"))
      (node (ref "U$1") (pin "P$14") (pinfunction "P$14_P$14") (pintype "bidirectional"))
    )
    (net (code "53") (name "P15") (class "Default")
      (node (ref "FORCE_LEFT") (pin "1") (pinfunction "1_1") (pintype "passive"))
      (node (ref "U$1") (pin "P$15") (pinfunction "P$15_P$15") (pintype "bidirectional"))
    )
    (net (code "54") (name "P16") (class "Default")
      (node (ref "FORCE_RIGHT") (pin "4") (pinfunction "1_4") (pintype "passive"))
      (node (ref "U$1") (pin "P$16") (pinfunction "P$16_P$16") (pintype "bidirectional"))
    )
    (net (code "55") (name "P17") (class "Default")
      (node (ref "FORCE_RIGHT") (pin "3") (pinfunction "1_3") (pintype "passive"))
      (node (ref "U$1") (pin "P$17") (pinfunction "P$17_P$17") (pintype "bidirectional"))
    )
    (net (code "56") (name "P18") (class "Default")
      (node (ref "FORCE_RIGHT") (pin "2") (pinfunction "1_2") (pintype "passive"))
      (node (ref "U$1") (pin "P$18") (pinfunction "P$18_P$18") (pintype "bidirectional"))
    )
    (net (code "57") (name "P19") (class "Default")
      (node (ref "FORCE_RIGHT") (pin "1") (pinfunction "1_1") (pintype "passive"))
      (node (ref "U$1") (pin "P$19") (pinfunction "P$19_P$19") (pintype "bidirectional"))
    )
    (net (code "58") (name "P20") (class "Default")
      (node (ref "23") (pin "1") (pinfunction "1_1") (pintype "passive"))
      (node (ref "LED") (pin "1") (pinfunction "1_1") (pintype "passive"))
      (node (ref "U$1") (pin "P$20") (pinfunction "P$20_P$20") (pintype "bidirectional"))
    )
    (net (code "59") (name "P21") (class "Default")
      (node (ref "P21") (pin "1") (pinfunction "1_1") (pintype "passive"))
      (node (ref "U$1") (pin "P$21") (pinfunction "P$21_P$21") (pintype "bidirectional"))
    )
    (net (code "60") (name "P22") (class "Default")
      (node (ref "P22") (pin "1") (pinfunction "1_1") (pintype "passive"))
      (node (ref "U$1") (pin "P$22") (pinfunction "P$22_P$22") (pintype "bidirectional"))
    )
    (net (code "61") (name "P23") (class "Default")
      (node (ref "24") (pin "2") (pinfunction "2_2") (pintype "passive"))
      (node (ref "P23") (pin "1") (pinfunction "1_1") (pintype "passive"))
      (node (ref "U$1") (pin "P$23") (pinfunction "P$23_P$23") (pintype "bidirectional"))
    )
    (net (code "62") (name "P24") (class "Default")
      (node (ref "12") (pin "1") (pinfunction "1_1") (pintype "passive"))
      (node (ref "Q1") (pin "2") (pinfunction "S_2") (pintype "passive"))
      (node (ref "U$1") (pin "P$24") (pinfunction "P$24_P$24") (pintype "bidirectional"))
    )
    (net (code "63") (name "P25") (class "Default")
      (node (ref "10") (pin "1") (pinfunction "1_1") (pintype "passive"))
      (node (ref "Q5") (pin "3") (pinfunction "D_3") (pintype "passive"))
      (node (ref "U$1") (pin "P$25") (pinfunction "P$25_P$25") (pintype "bidirectional"))
    )
    (net (code "64") (name "P28") (class "Default")
      (node (ref "27") (pin "1") (pinfunction "1_1") (pintype "passive"))
      (node (ref "C35") (pin "1") (pinfunction "1_1") (pintype "passive"))
      (node (ref "SW1") (pin "2") (pinfunction "1_2") (pintype "passive"))
      (node (ref "U$1") (pin "P$28") (pinfunction "P$28_P$28") (pintype "bidirectional"))
    )
    (net (code "65") (name "P29") (class "Default")
      (node (ref "26") (pin "1") (pinfunction "1_1") (pintype "passive"))
      (node (ref "C34") (pin "1") (pinfunction "1_1") (pintype "passive"))
      (node (ref "SW1") (pin "3") (pinfunction "1_3") (pintype "passive"))
      (node (ref "U$1") (pin "P$29") (pinfunction "P$29_P$29") (pintype "bidirectional"))
    )
    (net (code "66") (name "P30") (class "Default")
      (node (ref "25") (pin "1") (pinfunction "1_1") (pintype "passive"))
      (node (ref "C33") (pin "1") (pinfunction "1_1") (pintype "passive"))
      (node (ref "SW1") (pin "4") (pinfunction "1_4") (pintype "passive"))
      (node (ref "U$1") (pin "P$30") (pinfunction "P$30_P$30") (pintype "bidirectional"))
    )
    (net (code "67") (name "P32") (class "Default")
      (node (ref "JP2") (pin "1") (pinfunction "1_1") (pintype "passive"))
      (node (ref "U$1") (pin "P$32") (pinfunction "P$32_P$32") (pintype "bidirectional"))
    )
    (net (code "68") (name "P33") (class "Default")
      (node (ref "8") (pin "2") (pinfunction "2_2") (pintype "passive"))
      (node (ref "CSD8503KCS1") (pin "1") (pinfunction "G_1") (pintype "passive"))
      (node (ref "U$1") (pin "P$33") (pinfunction "P$33_P$33") (pintype "bidirectional"))
    )
    (net (code "69") (name "P34") (class "Default")
      (node (ref "28") (pin "1") (pinfunction "1_1") (pintype "passive"))
      (node (ref "C36") (pin "1") (pinfunction "1_1") (pintype "passive"))
      (node (ref "SW1") (pin "1") (pinfunction "1_1") (pintype "passive"))
      (node (ref "U$1") (pin "P$34") (pinfunction "P$34_P$34") (pintype "bidirectional"))
    )
    (net (code "70") (name "P35") (class "Default")
      (node (ref "RST") (pin "1") (pinfunction "1_1") (pintype "passive"))
      (node (ref "U$1") (pin "P$35") (pinfunction "P$35_P$35") (pintype "bidirectional"))
    )
    (net (code "71") (name "P36") (class "Default")
      (node (ref "JP2") (pin "5") (pinfunction "5_5") (pintype "passive"))
      (node (ref "U$1") (pin "P$36") (pinfunction "P$36_P$36") (pintype "bidirectional"))
    )
    (net (code "72") (name "P37") (class "Default")
      (node (ref "JP2") (pin "6") (pinfunction "6_6") (pintype "passive"))
      (node (ref "U$1") (pin "P$37") (pinfunction "P$37_P$37") (pintype "bidirectional"))
    )
    (net (code "73") (name "P38") (class "Default")
      (node (ref "29") (pin "1") (pinfunction "1_1") (pintype "passive"))
      (node (ref "U$1") (pin "P$38") (pinfunction "P$38_P$38") (pintype "bidirectional"))
    )
    (net (code "74") (name "P39") (class "Default")
      (node (ref "31") (pin "1") (pinfunction "1_1") (pintype "passive"))
      (node (ref "U$1") (pin "P$39") (pinfunction "P$39_P$39") (pintype "bidirectional"))
    )
    (net (code "75") (name "P40") (class "Default")
      (node (ref "33") (pin "1") (pinfunction "1_1") (pintype "passive"))
      (node (ref "U$1") (pin "P$40") (pinfunction "P$40_P$40") (pintype "bidirectional"))
    )
    (net (code "76") (name "RX3") (class "Default")
      (node (ref "P26") (pin "1") (pinfunction "1_1") (pintype "passive"))
      (node (ref "U$1") (pin "P$26") (pinfunction "P$26_P$26") (pintype "bidirectional"))
    )
    (net (code "77") (name "TIVA_RX") (class "Default")
      (node (ref "13") (pin "1") (pinfunction "1_1") (pintype "passive"))
      (node (ref "Q1") (pin "3") (pinfunction "D_3") (pintype "passive"))
      (node (ref "TX") (pin "1") (pinfunction "1_1") (pintype "passive"))
    )
    (net (code "78") (name "TIVA_TX") (class "Default")
      (node (ref "11") (pin "1") (pinfunction "1_1") (pintype "passive"))
      (node (ref "Q5") (pin "2") (pinfunction "S_2") (pintype "passive"))
      (node (ref "RX") (pin "1") (pinfunction "1_1") (pintype "passive"))
    )
    (net (code "79") (name "TX3") (class "Default")
      (node (ref "P27") (pin "1") (pinfunction "1_1") (pintype "passive"))
      (node (ref "U$1") (pin "P$27") (pinfunction "P$27_P$27") (pintype "bidirectional"))
    )
    (net (code "80") (name "VCC") (class "Default")
      (node (ref "1") (pin "2") (pinfunction "2_2") (pintype "passive"))
      (node (ref "1N4742") (pin "C") (pinfunction "C_C") (pintype "passive"))
      (node (ref "C1") (pin "+") (pinfunction "+_+") (pintype "passive"))
      (node (ref "C11") (pin "1") (pinfunction "1_1") (pintype "passive"))
      (node (ref "C8") (pin "1") (pinfunction "1_1") (pintype "passive"))
      (node (ref "CSD8503KCS1") (pin "2") (pinfunction "D_2") (pintype "passive"))
      (node (ref "FITPC") (pin "P$1") (pinfunction "P$1_P$1") (pintype "bidirectional"))
      (node (ref "MAIN_PWR_SW") (pin "2") (pinfunction "2_2") (pintype "passive"))
      (node (ref "U$4") (pin "P2") (pinfunction "P$2_P2") (pintype "bidirectional"))
    )
    (net (code "81") (name "unconnected-(JP2-Pad2)") (class "Default")
      (node (ref "JP2") (pin "2") (pinfunction "2_2") (pintype "passive"))
    )
    (net (code "82") (name "unconnected-(JP2-Pad3)") (class "Default")
      (node (ref "JP2") (pin "3") (pinfunction "3_3") (pintype "passive"))
    )
    (net (code "83") (name "unconnected-(JP2-Pad4)") (class "Default")
      (node (ref "JP2") (pin "4") (pinfunction "4_4") (pintype "passive"))
    )
    (net (code "84") (name "unconnected-(U$4-P$3-PadP3)") (class "Default")
      (node (ref "U$4") (pin "P3") (pinfunction "P$3_P3") (pintype "bidirectional"))
    )
    (net (code "85") (name "unconnected-(U1-NC-1-Pad1)") (class "Default")
      (node (ref "U1") (pin "1") (pinfunction "NC-1_1") (pintype "no_connect"))
    )
    (net (code "86") (name "unconnected-(U1-NC-2-Pad2)") (class "Default")
      (node (ref "U1") (pin "2") (pinfunction "NC-2_2") (pintype "no_connect"))
    )
    (net (code "87") (name "unconnected-(U2-NC-1-Pad1)") (class "Default")
      (node (ref "U2") (pin "1") (pinfunction "NC-1_1") (pintype "no_connect"))
    )
    (net (code "88") (name "unconnected-(U2-NC-2-Pad2)") (class "Default")
      (node (ref "U2") (pin "2") (pinfunction "NC-2_2") (pintype "no_connect"))
    )
    (net (code "89") (name "unconnected-(U3-NC-1-Pad1)") (class "Default")
      (node (ref "U3") (pin "1") (pinfunction "NC-1_1") (pintype "no_connect"))
    )
    (net (code "90") (name "unconnected-(U3-NC-2-Pad2)") (class "Default")
      (node (ref "U3") (pin "2") (pinfunction "NC-2_2") (pintype "no_connect"))
    )
    (net (code "91") (name "unconnected-(U4-NC-1-Pad1)") (class "Default")
      (node (ref "U4") (pin "1") (pinfunction "NC-1_1") (pintype "no_connect"))
    )
    (net (code "92") (name "unconnected-(U4-NC-2-Pad2)") (class "Default")
      (node (ref "U4") (pin "2") (pinfunction "NC-2_2") (pintype "no_connect"))
    )
    (net (code "93") (name "unconnected-(U5-NC-1-Pad1)") (class "Default")
      (node (ref "U5") (pin "1") (pinfunction "NC-1_1") (pintype "no_connect"))
    )
    (net (code "94") (name "unconnected-(U5-NC-2-Pad2)") (class "Default")
      (node (ref "U5") (pin "2") (pinfunction "NC-2_2") (pintype "no_connect"))
    )
    (net (code "95") (name "unconnected-(U6-NC-1-Pad1)") (class "Default")
      (node (ref "U6") (pin "1") (pinfunction "NC-1_1") (pintype "no_connect"))
    )
    (net (code "96") (name "unconnected-(U6-NC-2-Pad2)") (class "Default")
      (node (ref "U6") (pin "2") (pinfunction "NC-2_2") (pintype "no_connect"))
    )
    (net (code "97") (name "unconnected-(U7-NC-1-Pad1)") (class "Default")
      (node (ref "U7") (pin "1") (pinfunction "NC-1_1") (pintype "no_connect"))
    )
    (net (code "98") (name "unconnected-(U7-NC-2-Pad2)") (class "Default")
      (node (ref "U7") (pin "2") (pinfunction "NC-2_2") (pintype "no_connect"))
    )
  )
)
